# Uc_Ticketing_Master.net
KiCad netlist of a schematic drawn in Altium Designer
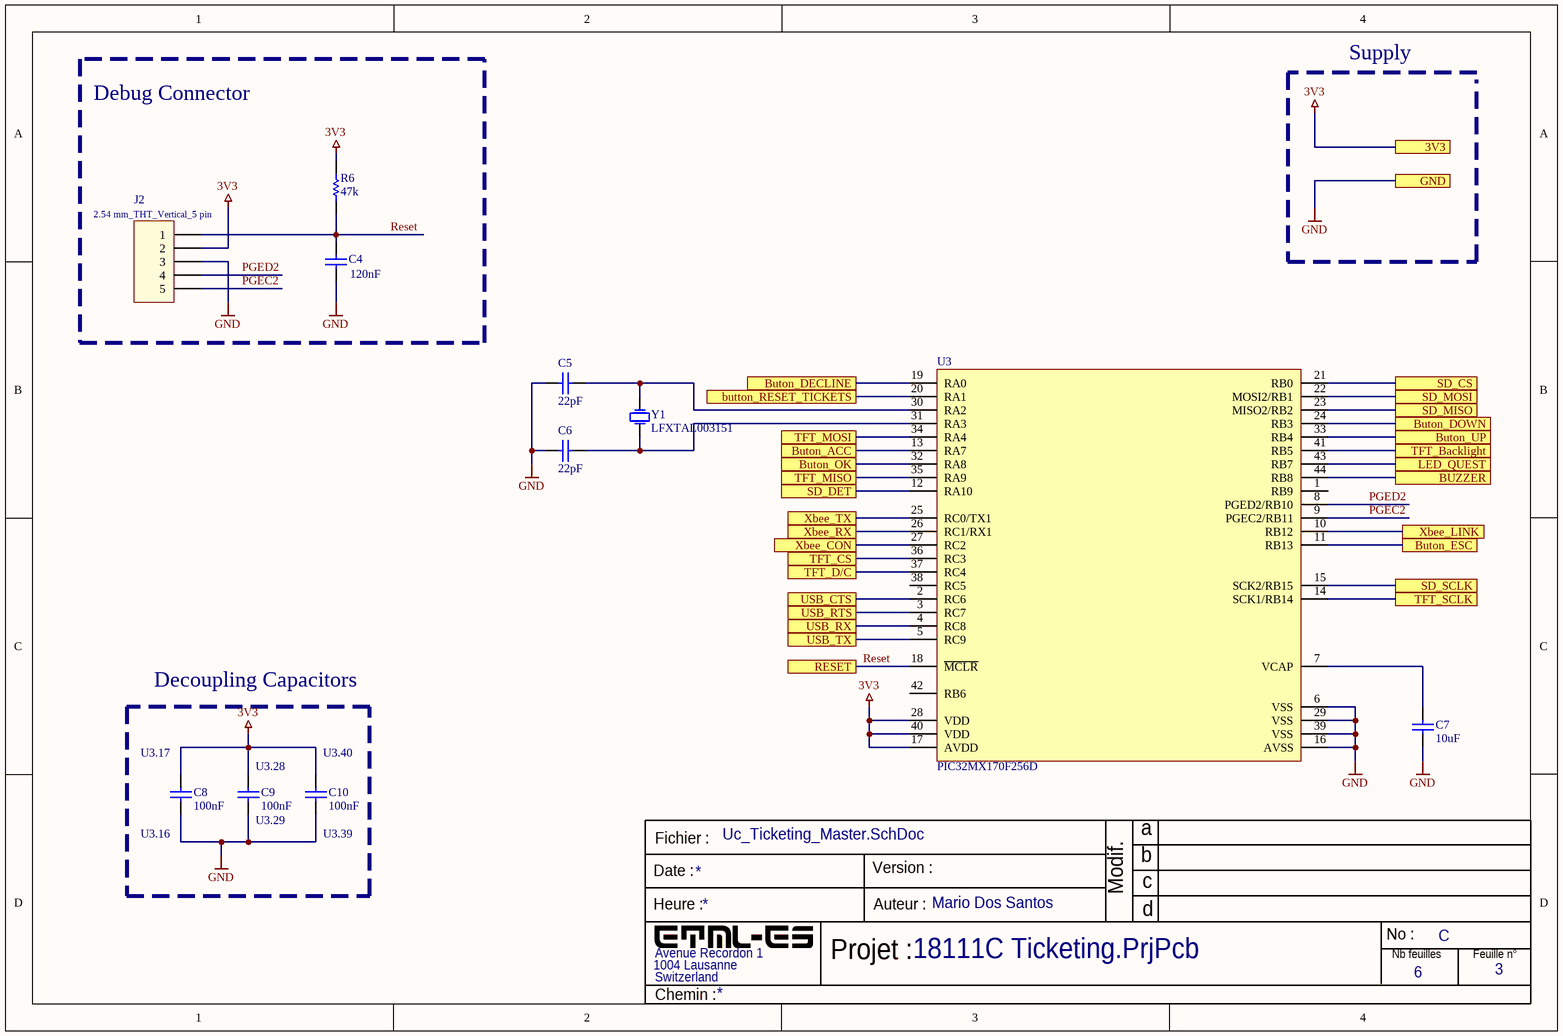
[diagram p0: Uc_Ticketing_Master.SchDoc]

(export (version "E")
  (design (tool "Eeschema 10.0.6"))
  (components
    (comp (ref "C4")
      (value "120nF")
      (footprint "6-0805_N")
      (description "Capacitor")
      (libsource (lib "Miscellaneous Devices") (part "Cap"))
    )
    (comp (ref "C5")
      (value "22pF")
      (footprint "6-0805_N")
      (description "VJ0805Y104KNAAT")
      (libsource (lib "2126_AffichageMatriciel") (part "CMP-2007-03167-1"))
    )
    (comp (ref "C6")
      (value "22pF")
      (footprint "6-0805_N")
      (description "VJ0805Y104KNAAT")
      (libsource (lib "2126_AffichageMatriciel") (part "CMP-2007-03167-1"))
    )
    (comp (ref "C7")
      (value "10uF")
      (footprint "6-0805_N")
      (description "Capacitor")
      (libsource (lib "Miscellaneous Devices") (part "Cap"))
    )
    (comp (ref "C8")
      (value "100nF")
      (footprint "6-0805_N")
      (description "Capacitor")
      (libsource (lib "Miscellaneous Devices") (part "Cap"))
    )
    (comp (ref "C9")
      (value "100nF")
      (footprint "6-0805_N")
      (description "Capacitor")
      (libsource (lib "Miscellaneous Devices") (part "Cap"))
    )
    (comp (ref "C10")
      (value "100nF")
      (footprint "6-0805_N")
      (description "Capacitor")
      (libsource (lib "Miscellaneous Devices") (part "Cap"))
    )
    (comp (ref "J2")
      (value "2.54 mm_THT_Vertical_5 pin")
      (footprint "61300511121")
      (description "Pin Header WR-PHD, pitch 2.54 mm, THT, Vertical, single row, 5 pin")
      (libsource (lib "ALTIUM-PHD_2_54_THT_PIN_HEADER_6130XX11121-rev18a") (part "61300511121"))
    )
    (comp (ref "R6")
      (value "47k")
      (footprint "RESC0805(2012)_L")
      (description "100K 0.125W 5% 0805 (2012 Metric)  SMD")
      (libsource (lib "Altium Content Vault") (part "CMP-1013-00122-1"))
    )
    (comp (ref "U3")
      (value "PIC32MX170F256D")
      (footprint "MCHP-TQFP-PT44_N")
      (libsource (lib "PCB_Ticketing_Master") (part "MCHP-PIC32MX2XXFXXXD-TQFP-44"))
    )
    (comp (ref "Y1")
      (value "LFXTAL003151")
      (footprint "LFXTAL003151REEL")
      (description "Crystal or Oscillator")
      (libsource (lib "2126_AffichageMatriciel") (part "LFXTAL003151REEL"))
    )
  )
  (nets
    (net (code "1") (name "/BUZZER") (class "Default")
      (node (ref "U3") (pin "44") (pinfunction "RB8_44") (pintype "passive"))
    )
    (net (code "2") (name "/Buton_ACC") (class "Default")
      (node (ref "U3") (pin "13") (pinfunction "RA7_13") (pintype "passive"))
    )
    (net (code "3") (name "/Buton_DECLINE") (class "Default")
      (node (ref "U3") (pin "19") (pinfunction "RA0_19") (pintype "passive"))
    )
    (net (code "4") (name "/Buton_DOWN") (class "Default")
      (node (ref "U3") (pin "24") (pinfunction "RB3_24") (pintype "passive"))
    )
    (net (code "5") (name "/Buton_ESC") (class "Default")
      (node (ref "U3") (pin "11") (pinfunction "RB13_11") (pintype "passive"))
    )
    (net (code "6") (name "/Buton_OK") (class "Default")
      (node (ref "U3") (pin "32") (pinfunction "RA8_32") (pintype "passive"))
    )
    (net (code "7") (name "/Buton_UP") (class "Default")
      (node (ref "U3") (pin "33") (pinfunction "RB4_33") (pintype "passive"))
    )
    (net (code "8") (name "/LED_QUEST") (class "Default")
      (node (ref "U3") (pin "43") (pinfunction "RB7_43") (pintype "passive"))
    )
    (net (code "9") (name "/PGEC2") (class "Default")
      (node (ref "J2") (pin "5") (pinfunction "5_5") (pintype "passive"))
      (node (ref "U3") (pin "9") (pinfunction "PGEC2/RB11_9") (pintype "passive"))
    )
    (net (code "10") (name "/PGED2") (class "Default")
      (node (ref "J2") (pin "4") (pinfunction "4_4") (pintype "passive"))
      (node (ref "U3") (pin "8") (pinfunction "PGED2/RB10_8") (pintype "passive"))
    )
    (net (code "11") (name "/Reset") (class "Default")
      (node (ref "C4") (pin "2") (pinfunction "2_2") (pintype "passive"))
      (node (ref "J2") (pin "1") (pinfunction "1_1") (pintype "passive"))
      (node (ref "R6") (pin "2") (pinfunction "2_2") (pintype "passive"))
      (node (ref "U3") (pin "18") (pinfunction "~{MCLR}_18") (pintype "passive"))
    )
    (net (code "12") (name "/SD_CS") (class "Default")
      (node (ref "U3") (pin "21") (pinfunction "RB0_21") (pintype "passive"))
    )
    (net (code "13") (name "/SD_DET") (class "Default")
      (node (ref "U3") (pin "12") (pinfunction "RA10_12") (pintype "passive"))
    )
    (net (code "14") (name "/SD_MISO") (class "Default")
      (node (ref "U3") (pin "23") (pinfunction "MISO2/RB2_23") (pintype "passive"))
    )
    (net (code "15") (name "/SD_MOSI") (class "Default")
      (node (ref "U3") (pin "22") (pinfunction "MOSI2/RB1_22") (pintype "passive"))
    )
    (net (code "16") (name "/SD_SCLK") (class "Default")
      (node (ref "U3") (pin "15") (pinfunction "SCK2/RB15_15") (pintype "passive"))
    )
    (net (code "17") (name "/TFT_Backlight") (class "Default")
      (node (ref "U3") (pin "41") (pinfunction "RB5_41") (pintype "passive"))
    )
    (net (code "18") (name "/TFT_CS") (class "Default")
      (node (ref "U3") (pin "36") (pinfunction "RC3_36") (pintype "passive"))
    )
    (net (code "19") (name "/TFT_D{slash}C") (class "Default")
      (node (ref "U3") (pin "37") (pinfunction "RC4_37") (pintype "passive"))
    )
    (net (code "20") (name "/TFT_MISO") (class "Default")
      (node (ref "U3") (pin "35") (pinfunction "RA9_35") (pintype "passive"))
    )
    (net (code "21") (name "/TFT_MOSI") (class "Default")
      (node (ref "U3") (pin "34") (pinfunction "RA4_34") (pintype "passive"))
    )
    (net (code "22") (name "/TFT_SCLK") (class "Default")
      (node (ref "U3") (pin "14") (pinfunction "SCK1/RB14_14") (pintype "passive"))
    )
    (net (code "23") (name "/USB_CTS") (class "Default")
      (node (ref "U3") (pin "2") (pinfunction "RC6_2") (pintype "passive"))
    )
    (net (code "24") (name "/USB_RTS") (class "Default")
      (node (ref "U3") (pin "3") (pinfunction "RC7_3") (pintype "passive"))
    )
    (net (code "25") (name "/USB_RX") (class "Default")
      (node (ref "U3") (pin "4") (pinfunction "RC8_4") (pintype "passive"))
    )
    (net (code "26") (name "/USB_TX") (class "Default")
      (node (ref "U3") (pin "5") (pinfunction "RC9_5") (pintype "passive"))
    )
    (net (code "27") (name "/Xbee_CON") (class "Default")
      (node (ref "U3") (pin "27") (pinfunction "RC2_27") (pintype "passive"))
    )
    (net (code "28") (name "/Xbee_LINK") (class "Default")
      (node (ref "U3") (pin "10") (pinfunction "RB12_10") (pintype "passive"))
    )
    (net (code "29") (name "/Xbee_RX") (class "Default")
      (node (ref "U3") (pin "26") (pinfunction "RC1/RX1_26") (pintype "passive"))
    )
    (net (code "30") (name "/Xbee_TX") (class "Default")
      (node (ref "U3") (pin "25") (pinfunction "RC0/TX1_25") (pintype "passive"))
    )
    (net (code "31") (name "/button_RESET_TICKETS") (class "Default")
      (node (ref "U3") (pin "20") (pinfunction "RA1_20") (pintype "passive"))
    )
    (net (code "32") (name "3V3") (class "Default")
      (node (ref "C10") (pin "2") (pinfunction "2_2") (pintype "passive"))
      (node (ref "C8") (pin "2") (pinfunction "2_2") (pintype "passive"))
      (node (ref "C9") (pin "2") (pinfunction "2_2") (pintype "passive"))
      (node (ref "J2") (pin "2") (pinfunction "2_2") (pintype "passive"))
      (node (ref "R6") (pin "1") (pinfunction "1_1") (pintype "passive"))
      (node (ref "U3") (pin "17") (pinfunction "AVDD_17") (pintype "passive"))
      (node (ref "U3") (pin "28") (pinfunction "VDD_28") (pintype "passive"))
      (node (ref "U3") (pin "40") (pinfunction "VDD_40") (pintype "passive"))
    )
    (net (code "33") (name "GND") (class "Default")
      (node (ref "C10") (pin "1") (pinfunction "1_1") (pintype "passive"))
      (node (ref "C4") (pin "1") (pinfunction "1_1") (pintype "passive"))
      (node (ref "C5") (pin "1") (pinfunction "1_1") (pintype "passive"))
      (node (ref "C6") (pin "1") (pinfunction "1_1") (pintype "passive"))
      (node (ref "C7") (pin "1") (pinfunction "1_1") (pintype "passive"))
      (node (ref "C8") (pin "1") (pinfunction "1_1") (pintype "passive"))
      (node (ref "C9") (pin "1") (pinfunction "1_1") (pintype "passive"))
      (node (ref "J2") (pin "3") (pinfunction "3_3") (pintype "passive"))
      (node (ref "U3") (pin "16") (pinfunction "AVSS_16") (pintype "passive"))
      (node (ref "U3") (pin "29") (pinfunction "VSS_29") (pintype "passive"))
      (node (ref "U3") (pin "39") (pinfunction "VSS_39") (pintype "passive"))
      (node (ref "U3") (pin "6") (pinfunction "VSS_6") (pintype "passive"))
    )
    (net (code "34") (name "Net-(U3-RA2)") (class "Default")
      (node (ref "C5") (pin "2") (pinfunction "2_2") (pintype "passive"))
      (node (ref "U3") (pin "30") (pinfunction "RA2_30") (pintype "passive"))
      (node (ref "Y1") (pin "1") (pinfunction "1_1") (pintype "passive"))
    )
    (net (code "35") (name "Net-(U3-RA3)") (class "Default")
      (node (ref "C6") (pin "2") (pinfunction "2_2") (pintype "passive"))
      (node (ref "U3") (pin "31") (pinfunction "RA3_31") (pintype "passive"))
      (node (ref "Y1") (pin "2") (pinfunction "2_2") (pintype "passive"))
    )
    (net (code "36") (name "Net-(U3-VCAP)") (class "Default")
      (node (ref "C7") (pin "2") (pinfunction "2_2") (pintype "passive"))
      (node (ref "U3") (pin "7") (pinfunction "VCAP_7") (pintype "passive"))
    )
    (net (code "37") (name "unconnected-(U3-RB6-Pad42)") (class "Default")
      (node (ref "U3") (pin "42") (pinfunction "RB6_42") (pintype "passive"))
    )
    (net (code "38") (name "unconnected-(U3-RB9-Pad1)") (class "Default")
      (node (ref "U3") (pin "1") (pinfunction "RB9_1") (pintype "passive"))
    )
    (net (code "39") (name "unconnected-(U3-RC5-Pad38)") (class "Default")
      (node (ref "U3") (pin "38") (pinfunction "RC5_38") (pintype "passive"))
    )
  )
)
